# PIO-Breakout.net
KiCad netlist of a schematic drawn in EAGLE
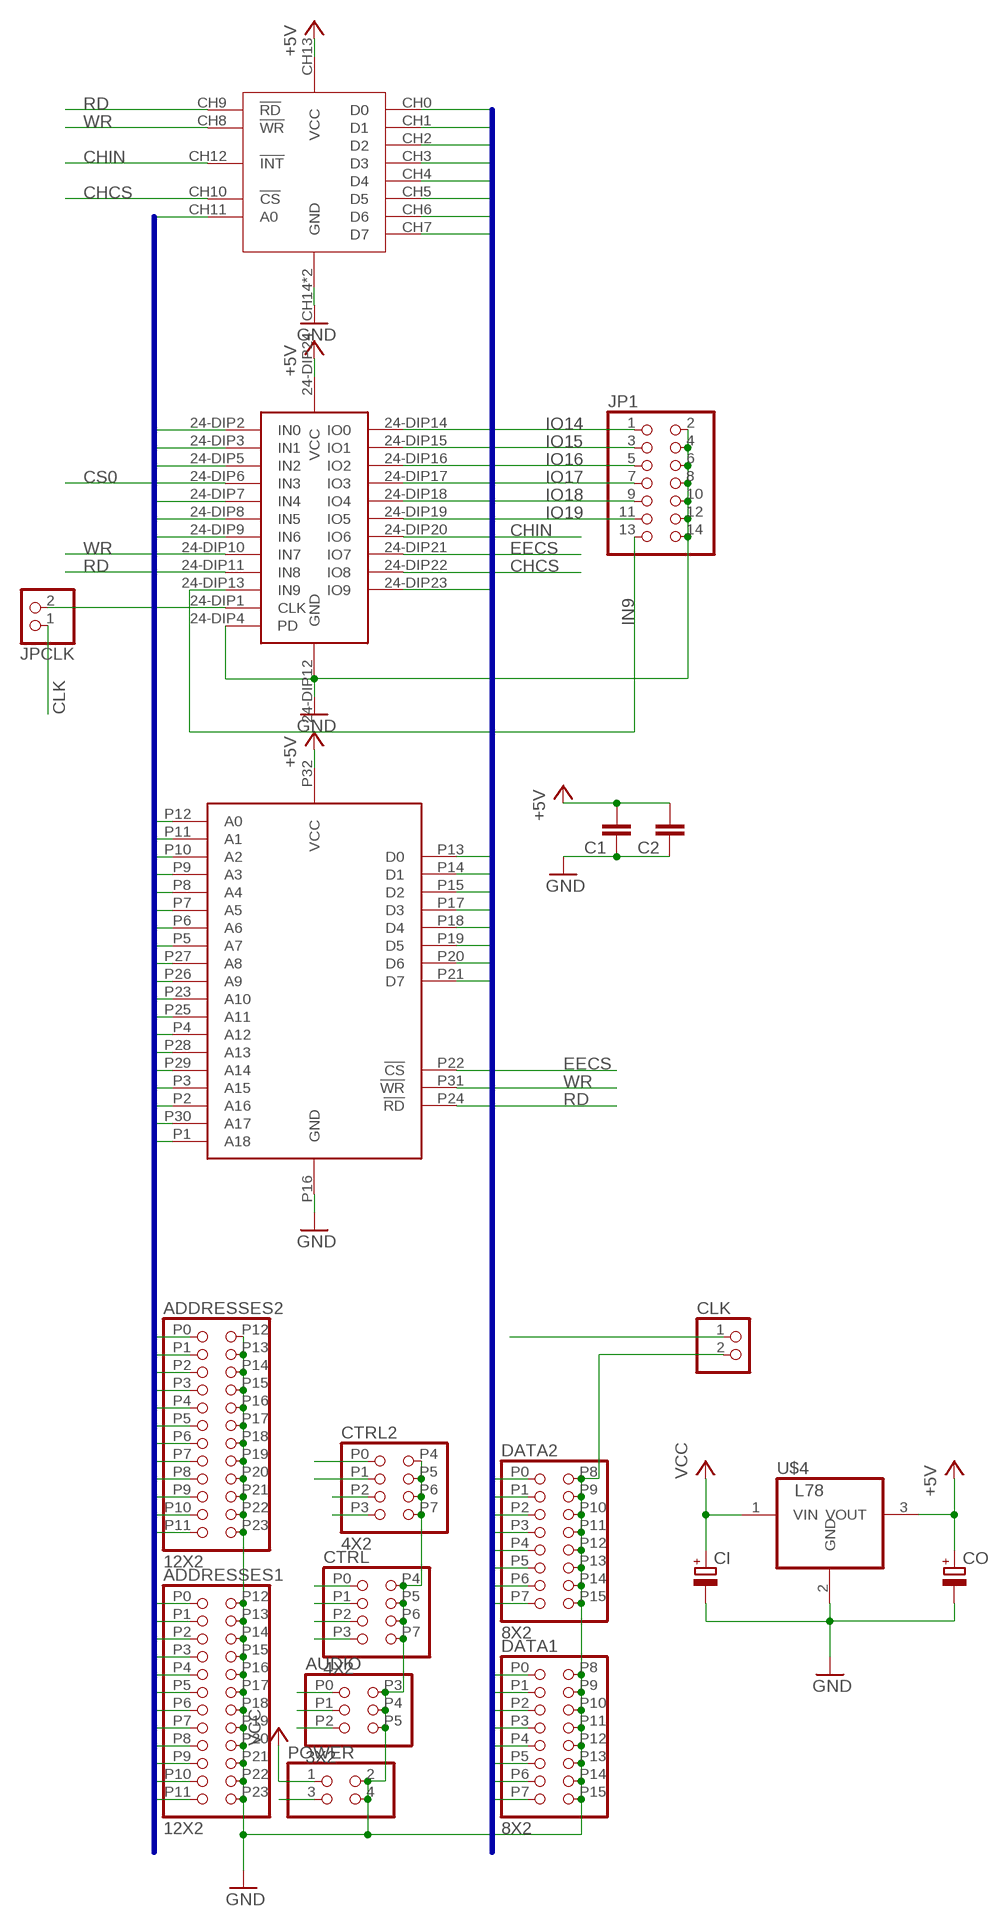
[diagram p0: schematic, sheet 1]

(export (version "E")
  (design (tool "Eeschema 10.0.6"))
  (components
    (comp (ref "ADDRESSES1")
      (value "12X2")
      (footprint "eagle-import:12X2")
      (libsource (lib "eagle-import") (part "12X2"))
    )
    (comp (ref "ADDRESSES2")
      (value "12X2")
      (footprint "eagle-import:12X2")
      (libsource (lib "eagle-import") (part "12X2"))
    )
    (comp (ref "AUDIO")
      (value "3X2")
      (footprint "eagle-import:3X2")
      (libsource (lib "eagle-import") (part "3X2"))
    )
    (comp (ref "C1")
      (value "C-EU025-024X044")
      (footprint "eagle-import:C025-024X044")
      (libsource (lib "eagle-import") (part "C-EU025-024X044"))
    )
    (comp (ref "C2")
      (value "C-EU025-024X044")
      (footprint "eagle-import:C025-024X044")
      (libsource (lib "eagle-import") (part "C-EU025-024X044"))
    )
    (comp (ref "CI")
      (value "CPOL-EUE2,5-6E")
      (footprint "eagle-import:E2,5-6E")
      (libsource (lib "eagle-import") (part "CPOL-EUE2,5-6E"))
    )
    (comp (ref "CLK")
      (value "PINHD-1X2")
      (footprint "eagle-import:1X02")
      (libsource (lib "eagle-import") (part "PINHD-1X2"))
    )
    (comp (ref "CO")
      (value "CPOL-EUE2,5-6E")
      (footprint "eagle-import:E2,5-6E")
      (libsource (lib "eagle-import") (part "CPOL-EUE2,5-6E"))
    )
    (comp (ref "CTRL")
      (value "4X2")
      (footprint "eagle-import:4X2")
      (libsource (lib "eagle-import") (part "4X2"))
    )
    (comp (ref "CTRL2")
      (value "4X2")
      (footprint "eagle-import:4X2")
      (libsource (lib "eagle-import") (part "4X2"))
    )
    (comp (ref "DATA1")
      (value "8X2")
      (footprint "eagle-import:8X2")
      (libsource (lib "eagle-import") (part "8X2"))
    )
    (comp (ref "DATA2")
      (value "8X2")
      (footprint "eagle-import:8X2")
      (libsource (lib "eagle-import") (part "8X2"))
    )
    (comp (ref "JP1")
      (value "PINHD-2X7")
      (footprint "eagle-import:2X07")
      (libsource (lib "eagle-import") (part "PINHD-2X7"))
    )
    (comp (ref "JPCLK")
      (value "PINHD-1X2")
      (footprint "eagle-import:1X02")
      (libsource (lib "eagle-import") (part "PINHD-1X2"))
    )
    (comp (ref "POWER")
      (value "PINHD-2X2")
      (footprint "eagle-import:2X02")
      (libsource (lib "eagle-import") (part "PINHD-2X2"))
    )
    (comp (ref "U$1")
      (value "AT29C040A")
      (footprint "eagle-import:DIP-32")
      (libsource (lib "eagle-import") (part "AT29C040A"))
    )
    (comp (ref "U$2")
      (value "ATF22V10C-10PU")
      (footprint "eagle-import:24-DIP")
      (libsource (lib "eagle-import") (part "ATF22V10C-10PU"))
    )
    (comp (ref "U$3")
      (value "CH375B-BOARD")
      (footprint "eagle-import:CH375B-BOARD")
      (libsource (lib "eagle-import") (part "CH375B-BOARD"))
    )
    (comp (ref "U$4")
      (value "L78")
      (footprint "eagle-import:TO-220-HEATSINK")
      (libsource (lib "eagle-import") (part "L78"))
    )
  )
  (nets
    (net (code "1") (name "+5V") (class "Default")
      (node (ref "C1") (pin "2") (pinfunction "2_2") (pintype "passive"))
      (node (ref "C2") (pin "2") (pinfunction "2_2") (pintype "passive"))
      (node (ref "CO") (pin "+") (pinfunction "+_+") (pintype "passive"))
      (node (ref "U$1") (pin "P32") (pinfunction "VCC_P32") (pintype "bidirectional"))
      (node (ref "U$2") (pin "24-DIP24") (pinfunction "VCC_24-DIP24") (pintype "bidirectional"))
      (node (ref "U$3") (pin "CH13") (pinfunction "VCC_CH13") (pintype "bidirectional"))
      (node (ref "U$4") (pin "3") (pinfunction "VOUT_3") (pintype "output"))
    )
    (net (code "2") (name "/A0") (class "Default")
      (node (ref "ADDRESSES1") (pin "P11") (pinfunction "P11_P11") (pintype "passive"))
      (node (ref "U$1") (pin "P12") (pinfunction "A0_P12") (pintype "bidirectional"))
      (node (ref "U$2") (pin "24-DIP2") (pinfunction "IN0_24-DIP2") (pintype "bidirectional"))
      (node (ref "U$3") (pin "CH11") (pinfunction "A0_CH11") (pintype "bidirectional"))
    )
    (net (code "3") (name "/A1") (class "Default")
      (node (ref "ADDRESSES2") (pin "P11") (pinfunction "P11_P11") (pintype "passive"))
      (node (ref "U$1") (pin "P11") (pinfunction "A1_P11") (pintype "bidirectional"))
      (node (ref "U$2") (pin "24-DIP3") (pinfunction "IN1_24-DIP3") (pintype "bidirectional"))
    )
    (net (code "4") (name "/A2") (class "Default")
      (node (ref "ADDRESSES1") (pin "P10") (pinfunction "P10_P10") (pintype "passive"))
      (node (ref "U$1") (pin "P10") (pinfunction "A2_P10") (pintype "bidirectional"))
      (node (ref "U$2") (pin "24-DIP5") (pinfunction "IN2_24-DIP5") (pintype "bidirectional"))
    )
    (net (code "5") (name "/A3") (class "Default")
      (node (ref "ADDRESSES2") (pin "P10") (pinfunction "P10_P10") (pintype "passive"))
      (node (ref "U$1") (pin "P9") (pinfunction "A3_P9") (pintype "bidirectional"))
    )
    (net (code "6") (name "/A4") (class "Default")
      (node (ref "ADDRESSES1") (pin "P9") (pinfunction "P9_P9") (pintype "passive"))
      (node (ref "U$1") (pin "P8") (pinfunction "A4_P8") (pintype "bidirectional"))
    )
    (net (code "7") (name "/A5") (class "Default")
      (node (ref "ADDRESSES2") (pin "P9") (pinfunction "P9_P9") (pintype "passive"))
      (node (ref "U$1") (pin "P7") (pinfunction "A5_P7") (pintype "bidirectional"))
    )
    (net (code "8") (name "/A6") (class "Default")
      (node (ref "ADDRESSES1") (pin "P8") (pinfunction "P8_P8") (pintype "passive"))
      (node (ref "U$1") (pin "P6") (pinfunction "A6_P6") (pintype "bidirectional"))
    )
    (net (code "9") (name "/A7") (class "Default")
      (node (ref "ADDRESSES2") (pin "P8") (pinfunction "P8_P8") (pintype "passive"))
      (node (ref "U$1") (pin "P5") (pinfunction "A7_P5") (pintype "bidirectional"))
    )
    (net (code "10") (name "/A8") (class "Default")
      (node (ref "ADDRESSES1") (pin "P7") (pinfunction "P7_P7") (pintype "passive"))
      (node (ref "U$1") (pin "P27") (pinfunction "A8_P27") (pintype "bidirectional"))
    )
    (net (code "11") (name "/A9") (class "Default")
      (node (ref "ADDRESSES2") (pin "P7") (pinfunction "P7_P7") (pintype "passive"))
      (node (ref "U$1") (pin "P26") (pinfunction "A9_P26") (pintype "bidirectional"))
    )
    (net (code "12") (name "/A10") (class "Default")
      (node (ref "ADDRESSES1") (pin "P6") (pinfunction "P6_P6") (pintype "passive"))
      (node (ref "U$1") (pin "P23") (pinfunction "A10_P23") (pintype "bidirectional"))
    )
    (net (code "13") (name "/A11") (class "Default")
      (node (ref "ADDRESSES2") (pin "P6") (pinfunction "P6_P6") (pintype "passive"))
      (node (ref "U$1") (pin "P25") (pinfunction "A11_P25") (pintype "bidirectional"))
    )
    (net (code "14") (name "/A12") (class "Default")
      (node (ref "ADDRESSES1") (pin "P5") (pinfunction "P5_P5") (pintype "passive"))
      (node (ref "U$1") (pin "P4") (pinfunction "A12_P4") (pintype "bidirectional"))
    )
    (net (code "15") (name "/A13") (class "Default")
      (node (ref "ADDRESSES2") (pin "P5") (pinfunction "P5_P5") (pintype "passive"))
      (node (ref "U$1") (pin "P28") (pinfunction "A13_P28") (pintype "bidirectional"))
    )
    (net (code "16") (name "/A14") (class "Default")
      (node (ref "ADDRESSES1") (pin "P4") (pinfunction "P4_P4") (pintype "passive"))
      (node (ref "U$1") (pin "P29") (pinfunction "A14_P29") (pintype "bidirectional"))
    )
    (net (code "17") (name "/A15") (class "Default")
      (node (ref "ADDRESSES2") (pin "P4") (pinfunction "P4_P4") (pintype "passive"))
      (node (ref "U$1") (pin "P3") (pinfunction "A15_P3") (pintype "bidirectional"))
    )
    (net (code "18") (name "/A16") (class "Default")
      (node (ref "ADDRESSES1") (pin "P3") (pinfunction "P3_P3") (pintype "passive"))
      (node (ref "U$1") (pin "P2") (pinfunction "A16_P2") (pintype "bidirectional"))
      (node (ref "U$2") (pin "24-DIP7") (pinfunction "IN4_24-DIP7") (pintype "bidirectional"))
    )
    (net (code "19") (name "/A17") (class "Default")
      (node (ref "ADDRESSES2") (pin "P3") (pinfunction "P3_P3") (pintype "passive"))
      (node (ref "U$1") (pin "P30") (pinfunction "A17_P30") (pintype "bidirectional"))
      (node (ref "U$2") (pin "24-DIP8") (pinfunction "IN5_24-DIP8") (pintype "bidirectional"))
    )
    (net (code "20") (name "/A18") (class "Default")
      (node (ref "ADDRESSES1") (pin "P2") (pinfunction "P2_P2") (pintype "passive"))
      (node (ref "U$1") (pin "P1") (pinfunction "A18_P1") (pintype "bidirectional"))
      (node (ref "U$2") (pin "24-DIP9") (pinfunction "IN6_24-DIP9") (pintype "bidirectional"))
    )
    (net (code "21") (name "/CHCS") (class "Default")
      (node (ref "U$2") (pin "24-DIP22") (pinfunction "IO8_24-DIP22") (pintype "bidirectional"))
      (node (ref "U$3") (pin "CH10") (pinfunction "~{CS}_CH10") (pintype "bidirectional"))
    )
    (net (code "22") (name "/CHIN") (class "Default")
      (node (ref "U$2") (pin "24-DIP20") (pinfunction "IO6_24-DIP20") (pintype "bidirectional"))
      (node (ref "U$3") (pin "CH12") (pinfunction "~{INT}_CH12") (pintype "bidirectional"))
    )
    (net (code "23") (name "/CLK") (class "Default")
      (node (ref "CLK") (pin "1") (pinfunction "1_1") (pintype "passive"))
      (node (ref "JPCLK") (pin "1") (pinfunction "1_1") (pintype "passive"))
    )
    (net (code "24") (name "/CS0") (class "Default")
      (node (ref "CTRL") (pin "P0") (pinfunction "P0_P0") (pintype "passive"))
      (node (ref "U$2") (pin "24-DIP6") (pinfunction "IN3_24-DIP6") (pintype "bidirectional"))
    )
    (net (code "25") (name "/D0") (class "Default")
      (node (ref "DATA1") (pin "P7") (pinfunction "P7_P7") (pintype "passive"))
      (node (ref "U$1") (pin "P13") (pinfunction "D0_P13") (pintype "bidirectional"))
      (node (ref "U$2") (pin "24-DIP23") (pinfunction "IO9_24-DIP23") (pintype "bidirectional"))
      (node (ref "U$3") (pin "CH0") (pinfunction "D0_CH0") (pintype "bidirectional"))
    )
    (net (code "26") (name "/D1") (class "Default")
      (node (ref "DATA2") (pin "P7") (pinfunction "P7_P7") (pintype "passive"))
      (node (ref "U$1") (pin "P14") (pinfunction "D1_P14") (pintype "bidirectional"))
      (node (ref "U$3") (pin "CH1") (pinfunction "D1_CH1") (pintype "bidirectional"))
    )
    (net (code "27") (name "/D2") (class "Default")
      (node (ref "DATA1") (pin "P6") (pinfunction "P6_P6") (pintype "passive"))
      (node (ref "U$1") (pin "P15") (pinfunction "D2_P15") (pintype "bidirectional"))
      (node (ref "U$3") (pin "CH2") (pinfunction "D2_CH2") (pintype "bidirectional"))
    )
    (net (code "28") (name "/D3") (class "Default")
      (node (ref "DATA2") (pin "P6") (pinfunction "P6_P6") (pintype "passive"))
      (node (ref "U$1") (pin "P17") (pinfunction "D3_P17") (pintype "bidirectional"))
      (node (ref "U$3") (pin "CH3") (pinfunction "D3_CH3") (pintype "bidirectional"))
    )
    (net (code "29") (name "/D4") (class "Default")
      (node (ref "DATA1") (pin "P5") (pinfunction "P5_P5") (pintype "passive"))
      (node (ref "U$1") (pin "P18") (pinfunction "D4_P18") (pintype "bidirectional"))
      (node (ref "U$3") (pin "CH4") (pinfunction "D4_CH4") (pintype "bidirectional"))
    )
    (net (code "30") (name "/D5") (class "Default")
      (node (ref "DATA2") (pin "P5") (pinfunction "P5_P5") (pintype "passive"))
      (node (ref "U$1") (pin "P19") (pinfunction "D5_P19") (pintype "bidirectional"))
      (node (ref "U$3") (pin "CH5") (pinfunction "D5_CH5") (pintype "bidirectional"))
    )
    (net (code "31") (name "/D6") (class "Default")
      (node (ref "DATA1") (pin "P4") (pinfunction "P4_P4") (pintype "passive"))
      (node (ref "U$1") (pin "P20") (pinfunction "D6_P20") (pintype "bidirectional"))
      (node (ref "U$3") (pin "CH6") (pinfunction "D6_CH6") (pintype "bidirectional"))
    )
    (net (code "32") (name "/D7") (class "Default")
      (node (ref "DATA2") (pin "P4") (pinfunction "P4_P4") (pintype "passive"))
      (node (ref "U$1") (pin "P21") (pinfunction "D7_P21") (pintype "bidirectional"))
      (node (ref "U$3") (pin "CH7") (pinfunction "D7_CH7") (pintype "bidirectional"))
    )
    (net (code "33") (name "/EECS") (class "Default")
      (node (ref "U$1") (pin "P22") (pinfunction "~{CS}_P22") (pintype "bidirectional"))
      (node (ref "U$2") (pin "24-DIP21") (pinfunction "IO7_24-DIP21") (pintype "bidirectional"))
    )
    (net (code "34") (name "/IN9") (class "Default")
      (node (ref "JP1") (pin "13") (pinfunction "13_13") (pintype "passive"))
      (node (ref "U$2") (pin "24-DIP13") (pinfunction "IN9_24-DIP13") (pintype "bidirectional"))
    )
    (net (code "35") (name "/IO14") (class "Default")
      (node (ref "JP1") (pin "1") (pinfunction "1_1") (pintype "passive"))
      (node (ref "U$2") (pin "24-DIP14") (pinfunction "IO0_24-DIP14") (pintype "bidirectional"))
    )
    (net (code "36") (name "/IO15") (class "Default")
      (node (ref "JP1") (pin "3") (pinfunction "3_3") (pintype "passive"))
      (node (ref "U$2") (pin "24-DIP15") (pinfunction "IO1_24-DIP15") (pintype "bidirectional"))
    )
    (net (code "37") (name "/IO16") (class "Default")
      (node (ref "JP1") (pin "5") (pinfunction "5_5") (pintype "passive"))
      (node (ref "U$2") (pin "24-DIP16") (pinfunction "IO2_24-DIP16") (pintype "bidirectional"))
    )
    (net (code "38") (name "/IO17") (class "Default")
      (node (ref "JP1") (pin "7") (pinfunction "7_7") (pintype "passive"))
      (node (ref "U$2") (pin "24-DIP17") (pinfunction "IO3_24-DIP17") (pintype "bidirectional"))
    )
    (net (code "39") (name "/IO18") (class "Default")
      (node (ref "JP1") (pin "9") (pinfunction "9_9") (pintype "passive"))
      (node (ref "U$2") (pin "24-DIP18") (pinfunction "IO4_24-DIP18") (pintype "bidirectional"))
    )
    (net (code "40") (name "/IO19") (class "Default")
      (node (ref "JP1") (pin "11") (pinfunction "11_11") (pintype "passive"))
      (node (ref "U$2") (pin "24-DIP19") (pinfunction "IO5_24-DIP19") (pintype "bidirectional"))
    )
    (net (code "41") (name "/RD") (class "Default")
      (node (ref "CTRL2") (pin "P2") (pinfunction "P2_P2") (pintype "passive"))
      (node (ref "U$1") (pin "P24") (pinfunction "~{RD}_P24") (pintype "bidirectional"))
      (node (ref "U$2") (pin "24-DIP11") (pinfunction "IN8_24-DIP11") (pintype "bidirectional"))
      (node (ref "U$3") (pin "CH9") (pinfunction "~{RD}_CH9") (pintype "bidirectional"))
    )
    (net (code "42") (name "/WR") (class "Default")
      (node (ref "CTRL2") (pin "P3") (pinfunction "P3_P3") (pintype "passive"))
      (node (ref "U$1") (pin "P31") (pinfunction "~{WR}_P31") (pintype "bidirectional"))
      (node (ref "U$2") (pin "24-DIP10") (pinfunction "IN7_24-DIP10") (pintype "bidirectional"))
      (node (ref "U$3") (pin "CH8") (pinfunction "~{WR}_CH8") (pintype "bidirectional"))
    )
    (net (code "43") (name "GND") (class "Default")
      (node (ref "ADDRESSES1") (pin "P12") (pinfunction "P12_P12") (pintype "passive"))
      (node (ref "ADDRESSES1") (pin "P13") (pinfunction "P13_P13") (pintype "passive"))
      (node (ref "ADDRESSES1") (pin "P14") (pinfunction "P14_P14") (pintype "passive"))
      (node (ref "ADDRESSES1") (pin "P15") (pinfunction "P15_P15") (pintype "passive"))
      (node (ref "ADDRESSES1") (pin "P16") (pinfunction "P16_P16") (pintype "passive"))
      (node (ref "ADDRESSES1") (pin "P17") (pinfunction "P17_P17") (pintype "passive"))
      (node (ref "ADDRESSES1") (pin "P18") (pinfunction "P18_P18") (pintype "passive"))
      (node (ref "ADDRESSES1") (pin "P19") (pinfunction "P19_P19") (pintype "passive"))
      (node (ref "ADDRESSES1") (pin "P20") (pinfunction "P20_P20") (pintype "passive"))
      (node (ref "ADDRESSES1") (pin "P21") (pinfunction "P21_P21") (pintype "passive"))
      (node (ref "ADDRESSES1") (pin "P22") (pinfunction "P22_P22") (pintype "passive"))
      (node (ref "ADDRESSES1") (pin "P23") (pinfunction "P23_P23") (pintype "passive"))
      (node (ref "ADDRESSES2") (pin "P12") (pinfunction "P12_P12") (pintype "passive"))
      (node (ref "ADDRESSES2") (pin "P13") (pinfunction "P13_P13") (pintype "passive"))
      (node (ref "ADDRESSES2") (pin "P14") (pinfunction "P14_P14") (pintype "passive"))
      (node (ref "ADDRESSES2") (pin "P15") (pinfunction "P15_P15") (pintype "passive"))
      (node (ref "ADDRESSES2") (pin "P16") (pinfunction "P16_P16") (pintype "passive"))
      (node (ref "ADDRESSES2") (pin "P17") (pinfunction "P17_P17") (pintype "passive"))
      (node (ref "ADDRESSES2") (pin "P18") (pinfunction "P18_P18") (pintype "passive"))
      (node (ref "ADDRESSES2") (pin "P19") (pinfunction "P19_P19") (pintype "passive"))
      (node (ref "ADDRESSES2") (pin "P20") (pinfunction "P20_P20") (pintype "passive"))
      (node (ref "ADDRESSES2") (pin "P21") (pinfunction "P21_P21") (pintype "passive"))
      (node (ref "ADDRESSES2") (pin "P22") (pinfunction "P22_P22") (pintype "passive"))
      (node (ref "ADDRESSES2") (pin "P23") (pinfunction "P23_P23") (pintype "passive"))
      (node (ref "AUDIO") (pin "P3") (pinfunction "P3_P3") (pintype "passive"))
      (node (ref "AUDIO") (pin "P4") (pinfunction "P4_P4") (pintype "passive"))
      (node (ref "AUDIO") (pin "P5") (pinfunction "P5_P5") (pintype "passive"))
      (node (ref "C1") (pin "1") (pinfunction "1_1") (pintype "passive"))
      (node (ref "C2") (pin "1") (pinfunction "1_1") (pintype "passive"))
      (node (ref "CI") (pin "-") (pinfunction "-_-") (pintype "passive"))
      (node (ref "CLK") (pin "2") (pinfunction "2_2") (pintype "passive"))
      (node (ref "CO") (pin "-") (pinfunction "-_-") (pintype "passive"))
      (node (ref "CTRL") (pin "P4") (pinfunction "P4_P4") (pintype "passive"))
      (node (ref "CTRL") (pin "P5") (pinfunction "P5_P5") (pintype "passive"))
      (node (ref "CTRL") (pin "P6") (pinfunction "P6_P6") (pintype "passive"))
      (node (ref "CTRL") (pin "P7") (pinfunction "P7_P7") (pintype "passive"))
      (node (ref "CTRL2") (pin "P4") (pinfunction "P4_P4") (pintype "passive"))
      (node (ref "CTRL2") (pin "P5") (pinfunction "P5_P5") (pintype "passive"))
      (node (ref "CTRL2") (pin "P6") (pinfunction "P6_P6") (pintype "passive"))
      (node (ref "CTRL2") (pin "P7") (pinfunction "P7_P7") (pintype "passive"))
      (node (ref "DATA1") (pin "P10") (pinfunction "P10_P10") (pintype "passive"))
      (node (ref "DATA1") (pin "P11") (pinfunction "P11_P11") (pintype "passive"))
      (node (ref "DATA1") (pin "P12") (pinfunction "P12_P12") (pintype "passive"))
      (node (ref "DATA1") (pin "P13") (pinfunction "P13_P13") (pintype "passive"))
      (node (ref "DATA1") (pin "P14") (pinfunction "P14_P14") (pintype "passive"))
      (node (ref "DATA1") (pin "P15") (pinfunction "P15_P15") (pintype "passive"))
      (node (ref "DATA1") (pin "P8") (pinfunction "P8_P8") (pintype "passive"))
      (node (ref "DATA1") (pin "P9") (pinfunction "P9_P9") (pintype "passive"))
      (node (ref "DATA2") (pin "P10") (pinfunction "P10_P10") (pintype "passive"))
      (node (ref "DATA2") (pin "P11") (pinfunction "P11_P11") (pintype "passive"))
      (node (ref "DATA2") (pin "P12") (pinfunction "P12_P12") (pintype "passive"))
      (node (ref "DATA2") (pin "P13") (pinfunction "P13_P13") (pintype "passive"))
      (node (ref "DATA2") (pin "P14") (pinfunction "P14_P14") (pintype "passive"))
      (node (ref "DATA2") (pin "P15") (pinfunction "P15_P15") (pintype "passive"))
      (node (ref "DATA2") (pin "P8") (pinfunction "P8_P8") (pintype "passive"))
      (node (ref "DATA2") (pin "P9") (pinfunction "P9_P9") (pintype "passive"))
      (node (ref "JP1") (pin "10") (pinfunction "10_10") (pintype "passive"))
      (node (ref "JP1") (pin "12") (pinfunction "12_12") (pintype "passive"))
      (node (ref "JP1") (pin "14") (pinfunction "14_14") (pintype "passive"))
      (node (ref "JP1") (pin "2") (pinfunction "2_2") (pintype "passive"))
      (node (ref "JP1") (pin "4") (pinfunction "4_4") (pintype "passive"))
      (node (ref "JP1") (pin "6") (pinfunction "6_6") (pintype "passive"))
      (node (ref "JP1") (pin "8") (pinfunction "8_8") (pintype "passive"))
      (node (ref "POWER") (pin "2") (pinfunction "2_2") (pintype "passive"))
      (node (ref "POWER") (pin "4") (pinfunction "4_4") (pintype "passive"))
      (node (ref "U$1") (pin "P16") (pinfunction "GND_P16") (pintype "bidirectional"))
      (node (ref "U$2") (pin "24-DIP12") (pinfunction "GND_24-DIP12") (pintype "bidirectional"))
      (node (ref "U$2") (pin "24-DIP4") (pinfunction "PD_24-DIP4") (pintype "bidirectional"))
      (node (ref "U$3") (pin "CH14") (pinfunction "GND_CH14") (pintype "bidirectional"))
      (node (ref "U$3") (pin "CH15") (pinfunction "GND_CH15") (pintype "bidirectional"))
      (node (ref "U$4") (pin "2") (pinfunction "GND_2") (pintype "power_in"))
    )
    (net (code "44") (name "Net-(U$2-CLK)") (class "Default")
      (node (ref "JPCLK") (pin "2") (pinfunction "2_2") (pintype "passive"))
      (node (ref "U$2") (pin "24-DIP1") (pinfunction "CLK_24-DIP1") (pintype "bidirectional"))
    )
    (net (code "45") (name "VCC") (class "Default")
      (node (ref "CI") (pin "+") (pinfunction "+_+") (pintype "passive"))
      (node (ref "POWER") (pin "1") (pinfunction "1_1") (pintype "passive"))
      (node (ref "U$4") (pin "1") (pinfunction "VIN_1") (pintype "input"))
    )
    (net (code "46") (name "unconnected-(ADDRESSES1-PadP0)") (class "Default")
      (node (ref "ADDRESSES1") (pin "P0") (pinfunction "P0_P0") (pintype "passive"))
    )
    (net (code "47") (name "unconnected-(ADDRESSES1-PadP1)") (class "Default")
      (node (ref "ADDRESSES1") (pin "P1") (pinfunction "P1_P1") (pintype "passive"))
    )
    (net (code "48") (name "unconnected-(ADDRESSES2-PadP0)") (class "Default")
      (node (ref "ADDRESSES2") (pin "P0") (pinfunction "P0_P0") (pintype "passive"))
    )
    (net (code "49") (name "unconnected-(ADDRESSES2-PadP1)") (class "Default")
      (node (ref "ADDRESSES2") (pin "P1") (pinfunction "P1_P1") (pintype "passive"))
    )
    (net (code "50") (name "unconnected-(ADDRESSES2-PadP2)") (class "Default")
      (node (ref "ADDRESSES2") (pin "P2") (pinfunction "P2_P2") (pintype "passive"))
    )
    (net (code "51") (name "unconnected-(AUDIO-PadP0)") (class "Default")
      (node (ref "AUDIO") (pin "P0") (pinfunction "P0_P0") (pintype "passive"))
    )
    (net (code "52") (name "unconnected-(AUDIO-PadP1)") (class "Default")
      (node (ref "AUDIO") (pin "P1") (pinfunction "P1_P1") (pintype "passive"))
    )
    (net (code "53") (name "unconnected-(AUDIO-PadP2)") (class "Default")
      (node (ref "AUDIO") (pin "P2") (pinfunction "P2_P2") (pintype "passive"))
    )
    (net (code "54") (name "unconnected-(CTRL-PadP1)") (class "Default")
      (node (ref "CTRL") (pin "P1") (pinfunction "P1_P1") (pintype "passive"))
    )
    (net (code "55") (name "unconnected-(CTRL-PadP2)") (class "Default")
      (node (ref "CTRL") (pin "P2") (pinfunction "P2_P2") (pintype "passive"))
    )
    (net (code "56") (name "unconnected-(CTRL-PadP3)") (class "Default")
      (node (ref "CTRL") (pin "P3") (pinfunction "P3_P3") (pintype "passive"))
    )
    (net (code "57") (name "unconnected-(CTRL2-PadP0)") (class "Default")
      (node (ref "CTRL2") (pin "P0") (pinfunction "P0_P0") (pintype "passive"))
    )
    (net (code "58") (name "unconnected-(CTRL2-PadP1)") (class "Default")
      (node (ref "CTRL2") (pin "P1") (pinfunction "P1_P1") (pintype "passive"))
    )
    (net (code "59") (name "unconnected-(DATA1-PadP0)") (class "Default")
      (node (ref "DATA1") (pin "P0") (pinfunction "P0_P0") (pintype "passive"))
    )
    (net (code "60") (name "unconnected-(DATA1-PadP1)") (class "Default")
      (node (ref "DATA1") (pin "P1") (pinfunction "P1_P1") (pintype "passive"))
    )
    (net (code "61") (name "unconnected-(DATA1-PadP2)") (class "Default")
      (node (ref "DATA1") (pin "P2") (pinfunction "P2_P2") (pintype "passive"))
    )
    (net (code "62") (name "unconnected-(DATA1-PadP3)") (class "Default")
      (node (ref "DATA1") (pin "P3") (pinfunction "P3_P3") (pintype "passive"))
    )
    (net (code "63") (name "unconnected-(DATA2-PadP0)") (class "Default")
      (node (ref "DATA2") (pin "P0") (pinfunction "P0_P0") (pintype "passive"))
    )
    (net (code "64") (name "unconnected-(DATA2-PadP1)") (class "Default")
      (node (ref "DATA2") (pin "P1") (pinfunction "P1_P1") (pintype "passive"))
    )
    (net (code "65") (name "unconnected-(DATA2-PadP2)") (class "Default")
      (node (ref "DATA2") (pin "P2") (pinfunction "P2_P2") (pintype "passive"))
    )
    (net (code "66") (name "unconnected-(DATA2-PadP3)") (class "Default")
      (node (ref "DATA2") (pin "P3") (pinfunction "P3_P3") (pintype "passive"))
    )
    (net (code "67") (name "unconnected-(POWER-Pad3)") (class "Default")
      (node (ref "POWER") (pin "3") (pinfunction "3_3") (pintype "passive"))
    )
  )
)
